# Power.net
KiCad netlist of a schematic drawn in Altium Designer
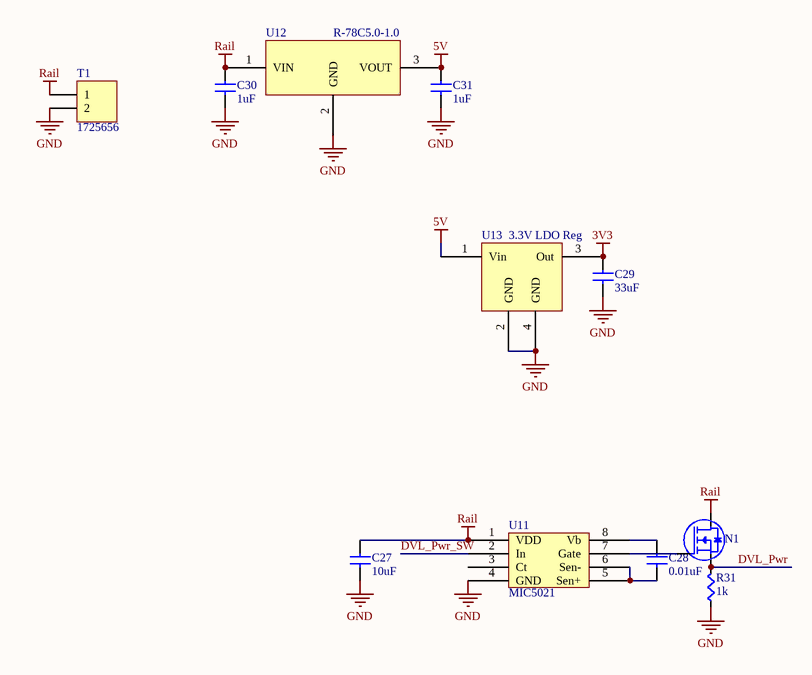
[diagram p0: Power.SchDoc]

(export (version "E")
  (design (tool "Eeschema 10.0.6"))
  (components
    (comp (ref "C27")
      (value "10uF")
      (footprint "CAPC0805")
      (fields (field (name "Comment") "Cap"))
      (libsource (lib "SubjuGator8") (part "Cap"))
    )
    (comp (ref "C28")
      (value "0.01uF")
      (footprint "CAPC0805")
      (fields (field (name "Comment") "Cap"))
      (libsource (lib "SubjuGator8") (part "Cap"))
    )
    (comp (ref "C29")
      (value "33uF")
      (footprint "CAPC1206")
      (fields (field (name "Comment") "Cap"))
      (libsource (lib "SubjuGator8") (part "Cap"))
    )
    (comp (ref "C30")
      (value "1uF")
      (footprint "CAPC0603")
      (fields (field (name "Comment") "Cap"))
      (libsource (lib "SubjuGator8") (part "Cap"))
    )
    (comp (ref "C31")
      (value "1uF")
      (footprint "CAPC0603")
      (fields (field (name "Comment") "Cap"))
      (libsource (lib "SubjuGator8") (part "Cap"))
    )
    (comp (ref "N1")
      (value "NMOSFET_TO-220")
      (footprint "TO-220AB Heatsink")
      (description "NMOSFET_TO-220-Template")
      (libsource (lib "SubjuGator8") (part "NMOSFET_TO-220"))
    )
    (comp (ref "R31")
      (value "1k")
      (footprint "RES0603")
      (fields (field (name "Comment") "Res"))
      (libsource (lib "SubjuGator8") (part "Res"))
    )
    (comp (ref "T1")
      (value "1725656")
      (footprint "1725656")
      (description "CONN TERM BLOCK 2.54MM 2POS")
      (libsource (lib "SubjuGator8") (part "1725656"))
    )
    (comp (ref "U11")
      (value "MIC5021")
      (footprint "MIC5021")
      (description "IC DRIVER MOSFET HISIDE HS 8SOIC")
      (libsource (lib "SubjuGator8") (part "MIC5021"))
    )
    (comp (ref "U12")
      (value "R-78C5.0-1.0")
      (footprint "R-78C5.0-1.0")
      (description "CONV DC/DC 1A 5V OUT SIP VERT")
      (libsource (lib "SubjuGator8") (part "R-78C5.0-1.0"))
    )
    (comp (ref "U13")
      (value "3.3V LDO Reg")
      (footprint "SOT23-4n")
      (description "IC REG LDO 3.3V 1A SOT223")
      (libsource (lib "SubjuGator8") (part "LM3940IMPX-3.3"))
    )
  )
  (nets
    (net (code "1") (name "/DVL_Pwr") (class "Default")
      (node (ref "N1") (pin "S") (pinfunction "S_S") (pintype "passive"))
      (node (ref "R31") (pin "1") (pinfunction "A_1") (pintype "passive"))
    )
    (net (code "2") (name "/DVL_Pwr_SW") (class "Default")
      (node (ref "U11") (pin "2") (pinfunction "In_2") (pintype "passive"))
    )
    (net (code "3") (name "3V3") (class "Default")
      (node (ref "C29") (pin "1") (pinfunction "A_1") (pintype "passive"))
      (node (ref "U13") (pin "3") (pinfunction "Out_3") (pintype "passive"))
    )
    (net (code "4") (name "5V") (class "Default")
      (node (ref "C31") (pin "1") (pinfunction "A_1") (pintype "passive"))
      (node (ref "U12") (pin "3") (pinfunction "VOUT_3") (pintype "passive"))
      (node (ref "U13") (pin "1") (pinfunction "Vin_1") (pintype "passive"))
    )
    (net (code "5") (name "GND") (class "Default")
      (node (ref "C27") (pin "2") (pinfunction "B_2") (pintype "passive"))
      (node (ref "C29") (pin "2") (pinfunction "B_2") (pintype "passive"))
      (node (ref "C30") (pin "2") (pinfunction "B_2") (pintype "passive"))
      (node (ref "C31") (pin "2") (pinfunction "B_2") (pintype "passive"))
      (node (ref "R31") (pin "2") (pinfunction "B_2") (pintype "passive"))
      (node (ref "T1") (pin "2") (pinfunction "2_2") (pintype "passive"))
      (node (ref "U11") (pin "4") (pinfunction "GND_4") (pintype "passive"))
      (node (ref "U12") (pin "2") (pinfunction "GND_2") (pintype "power_in"))
      (node (ref "U13") (pin "2") (pinfunction "GND_2") (pintype "passive"))
      (node (ref "U13") (pin "4") (pinfunction "GND_4") (pintype "passive"))
    )
    (net (code "6") (name "Net-(C28-A)") (class "Default")
      (node (ref "C28") (pin "1") (pinfunction "A_1") (pintype "passive"))
      (node (ref "U11") (pin "8") (pinfunction "Vb_8") (pintype "passive"))
    )
    (net (code "7") (name "Net-(C28-B)") (class "Default")
      (node (ref "C28") (pin "2") (pinfunction "B_2") (pintype "passive"))
      (node (ref "U11") (pin "5") (pinfunction "Sen+_5") (pintype "passive"))
      (node (ref "U11") (pin "6") (pinfunction "Sen-_6") (pintype "passive"))
    )
    (net (code "8") (name "Net-(U11-Gate)") (class "Default")
      (node (ref "N1") (pin "G") (pinfunction "G_G") (pintype "passive"))
      (node (ref "U11") (pin "7") (pinfunction "Gate_7") (pintype "passive"))
    )
    (net (code "9") (name "Rail") (class "Default")
      (node (ref "C27") (pin "1") (pinfunction "A_1") (pintype "passive"))
      (node (ref "C30") (pin "1") (pinfunction "A_1") (pintype "passive"))
      (node (ref "N1") (pin "D") (pinfunction "D_D") (pintype "passive"))
      (node (ref "T1") (pin "1") (pinfunction "1_1") (pintype "passive"))
      (node (ref "U11") (pin "1") (pinfunction "VDD_1") (pintype "passive"))
      (node (ref "U12") (pin "1") (pinfunction "VIN_1") (pintype "passive"))
    )
    (net (code "10") (name "unconnected-(U11-Ct-Pad3)") (class "Default")
      (node (ref "U11") (pin "3") (pinfunction "Ct_3") (pintype "passive"))
    )
  )
)
